# idro900ma.net
KiCad netlist of a schematic drawn in Altium Designer
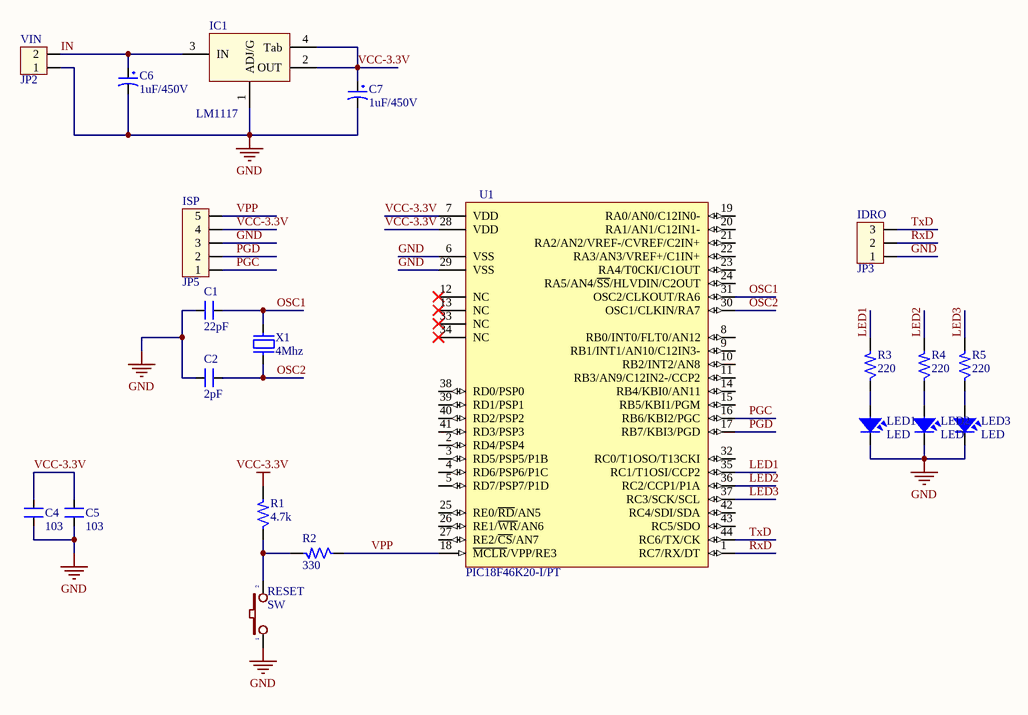
[diagram p0: idro900ma.SchDoc]

(export (version "E")
  (design (tool "Eeschema 10.0.6"))
  (components
    (comp (ref "C1")
      (value "22pF")
      (footprint "SM-0805")
      (description "Cap SMD")
      (libsource (lib "syhaunguyen") (part "CM"))
    )
    (comp (ref "C2")
      (value "2pF")
      (footprint "SM-0805")
      (description "Cap SMD")
      (libsource (lib "syhaunguyen") (part "CM"))
    )
    (comp (ref "C4")
      (value "103")
      (footprint "SM-0805")
      (description "Cap SMD")
      (libsource (lib "syhaunguyen") (part "CM"))
    )
    (comp (ref "C5")
      (value "103")
      (footprint "SM-0805")
      (description "Cap SMD")
      (libsource (lib "syhaunguyen") (part "CM"))
    )
    (comp (ref "C6")
      (value "1uF/450V")
      (footprint "SM-0805")
      (description "Cap 4700uF/50V")
      (libsource (lib "syhaunguyen") (part "CP8"))
    )
    (comp (ref "C7")
      (value "1uF/450V")
      (footprint "SM-0805")
      (description "Cap 4700uF/50V")
      (libsource (lib "syhaunguyen") (part "CP8"))
    )
    (comp (ref "IC1")
      (value "LM1117")
      (footprint "SOT223-4N")
      (description "3v3")
      (libsource (lib "syhaunguyen") (part "LM1117"))
    )
    (comp (ref "IDRO")
      (value "JP3")
      (footprint "CON3")
      (description "Connector 3")
      (libsource (lib "syhaunguyen") (part "Con3"))
    )
    (comp (ref "ISP")
      (value "JP5")
      (footprint "CON5")
      (description "Connector 5")
      (libsource (lib "syhaunguyen") (part "Con5"))
    )
    (comp (ref "LED1")
      (value "LED")
      (footprint "LED1206-Green")
      (description "LED Single colour Green and Red")
      (libsource (lib "syhaunguyen") (part "LED"))
    )
    (comp (ref "LED2")
      (value "LED")
      (footprint "LED1206-Green")
      (description "LED Single colour Green and Red")
      (libsource (lib "syhaunguyen") (part "LED"))
    )
    (comp (ref "LED3")
      (value "LED")
      (footprint "LED1206-Green")
      (description "LED Single colour Green and Red")
      (libsource (lib "syhaunguyen") (part "LED"))
    )
    (comp (ref "R1")
      (value "4.7k")
      (footprint "SM-0805")
      (description "Resistor 1/4W")
      (libsource (lib "syhaunguyen") (part "R"))
    )
    (comp (ref "R2")
      (value "330")
      (footprint "SM-0805")
      (description "Resistor 1/4W")
      (libsource (lib "syhaunguyen") (part "R"))
    )
    (comp (ref "R3")
      (value "220")
      (footprint "SM-0805")
      (description "Resistor 1/4W")
      (libsource (lib "syhaunguyen") (part "R"))
    )
    (comp (ref "R4")
      (value "220")
      (footprint "SM-0805")
      (description "Resistor 1/4W")
      (libsource (lib "syhaunguyen") (part "R"))
    )
    (comp (ref "R5")
      (value "220")
      (footprint "SM-0805")
      (description "Resistor 1/4W")
      (libsource (lib "syhaunguyen") (part "R"))
    )
    (comp (ref "RESET")
      (value "SW")
      (footprint "SW2")
      (description "Switch button 2 pin")
      (libsource (lib "syhaunguyen") (part "SW2"))
    )
    (comp (ref "U1")
      (value "PIC18F46K20-I/PT")
      (footprint "TQFP-PT44_N")
      (fields (field (name "PUBLISHER") "Altium Limited"))
      (libsource (lib "Microchip Microcontroller 8-Bit PIC18") (part "PIC18F46K20-I/PT"))
    )
    (comp (ref "VIN")
      (value "JP2")
      (footprint "CON2")
      (description "Connector 2")
      (libsource (lib "syhaunguyen") (part "Con2"))
    )
    (comp (ref "X1")
      (value "4Mhz")
      (footprint "XT2")
      (description "Crystal For all Crystal 2pin.")
      (libsource (lib "syhaunguyen") (part "XT2"))
    )
  )
  (nets
    (net (code "1") (name "/IN") (class "Default")
      (node (ref "C6") (pin "1") (pinfunction "1_1") (pintype "passive"))
      (node (ref "IC1") (pin "3") (pinfunction "IN_3") (pintype "passive"))
      (node (ref "VIN") (pin "2") (pinfunction "2_2") (pintype "passive"))
    )
    (net (code "2") (name "/LED1") (class "Default")
      (node (ref "R3") (pin "2") (pinfunction "2_2") (pintype "passive"))
      (node (ref "U1") (pin "35") (pinfunction "RC1/T1OSI/CCP2_35") (pintype "bidirectional"))
    )
    (net (code "3") (name "/LED2") (class "Default")
      (node (ref "R4") (pin "2") (pinfunction "2_2") (pintype "passive"))
      (node (ref "U1") (pin "36") (pinfunction "RC2/CCP1/P1A_36") (pintype "bidirectional"))
    )
    (net (code "4") (name "/LED3") (class "Default")
      (node (ref "R5") (pin "2") (pinfunction "2_2") (pintype "passive"))
      (node (ref "U1") (pin "37") (pinfunction "RC3/SCK/SCL_37") (pintype "bidirectional"))
    )
    (net (code "5") (name "/OSC1") (class "Default")
      (node (ref "C1") (pin "2") (pinfunction "2_2") (pintype "passive"))
      (node (ref "U1") (pin "31") (pinfunction "OSC2/CLKOUT/RA6_31") (pintype "bidirectional"))
      (node (ref "X1") (pin "2") (pinfunction "2_2") (pintype "passive"))
    )
    (net (code "6") (name "/OSC2") (class "Default")
      (node (ref "C2") (pin "2") (pinfunction "2_2") (pintype "passive"))
      (node (ref "U1") (pin "30") (pinfunction "OSC1/CLKIN/RA7_30") (pintype "bidirectional"))
      (node (ref "X1") (pin "1") (pinfunction "1_1") (pintype "passive"))
    )
    (net (code "7") (name "/PGC") (class "Default")
      (node (ref "ISP") (pin "1") (pinfunction "1_1") (pintype "passive"))
      (node (ref "U1") (pin "16") (pinfunction "RB6/KBI2/PGC_16") (pintype "bidirectional"))
    )
    (net (code "8") (name "/PGD") (class "Default")
      (node (ref "ISP") (pin "2") (pinfunction "2_2") (pintype "passive"))
      (node (ref "U1") (pin "17") (pinfunction "RB7/KBI3/PGD_17") (pintype "bidirectional"))
    )
    (net (code "9") (name "/RxD") (class "Default")
      (node (ref "IDRO") (pin "2") (pinfunction "2_2") (pintype "passive"))
      (node (ref "U1") (pin "1") (pinfunction "RC7/RX/DT_1") (pintype "bidirectional"))
    )
    (net (code "10") (name "/TxD") (class "Default")
      (node (ref "IDRO") (pin "3") (pinfunction "3_3") (pintype "passive"))
      (node (ref "U1") (pin "44") (pinfunction "RC6/TX/CK_44") (pintype "bidirectional"))
    )
    (net (code "11") (name "/VPP") (class "Default")
      (node (ref "ISP") (pin "5") (pinfunction "5_5") (pintype "passive"))
      (node (ref "R2") (pin "1") (pinfunction "1_1") (pintype "passive"))
      (node (ref "U1") (pin "18") (pinfunction "~{MCLR}/VPP/RE3_18") (pintype "input"))
    )
    (net (code "12") (name "GND") (class "Default")
      (node (ref "C1") (pin "1") (pinfunction "1_1") (pintype "passive"))
      (node (ref "C2") (pin "1") (pinfunction "1_1") (pintype "passive"))
      (node (ref "C4") (pin "1") (pinfunction "1_1") (pintype "passive"))
      (node (ref "C5") (pin "1") (pinfunction "1_1") (pintype "passive"))
      (node (ref "C6") (pin "2") (pinfunction "2_2") (pintype "passive"))
      (node (ref "C7") (pin "2") (pinfunction "2_2") (pintype "passive"))
      (node (ref "IC1") (pin "1") (pinfunction "ADJ/G_1") (pintype "passive"))
      (node (ref "IDRO") (pin "1") (pinfunction "1_1") (pintype "passive"))
      (node (ref "ISP") (pin "3") (pinfunction "3_3") (pintype "passive"))
      (node (ref "LED1") (pin "2") (pinfunction "2_2") (pintype "passive"))
      (node (ref "LED2") (pin "2") (pinfunction "2_2") (pintype "passive"))
      (node (ref "LED3") (pin "2") (pinfunction "2_2") (pintype "passive"))
      (node (ref "RESET") (pin "1") (pinfunction "1_1") (pintype "passive"))
      (node (ref "U1") (pin "29") (pinfunction "VSS_29") (pintype "power_in"))
      (node (ref "U1") (pin "6") (pinfunction "VSS_6") (pintype "power_in"))
      (node (ref "VIN") (pin "1") (pinfunction "1_1") (pintype "passive"))
    )
    (net (code "13") (name "Net-(LED1-Pad1)") (class "Default")
      (node (ref "LED1") (pin "1") (pinfunction "1_1") (pintype "passive"))
      (node (ref "R3") (pin "1") (pinfunction "1_1") (pintype "passive"))
    )
    (net (code "14") (name "Net-(LED2-Pad1)") (class "Default")
      (node (ref "LED2") (pin "1") (pinfunction "1_1") (pintype "passive"))
      (node (ref "R4") (pin "1") (pinfunction "1_1") (pintype "passive"))
    )
    (net (code "15") (name "Net-(LED3-Pad1)") (class "Default")
      (node (ref "LED3") (pin "1") (pinfunction "1_1") (pintype "passive"))
      (node (ref "R5") (pin "1") (pinfunction "1_1") (pintype "passive"))
    )
    (net (code "16") (name "Net-(R1-Pad1)") (class "Default")
      (node (ref "R1") (pin "1") (pinfunction "1_1") (pintype "passive"))
      (node (ref "R2") (pin "2") (pinfunction "2_2") (pintype "passive"))
      (node (ref "RESET") (pin "2") (pinfunction "2_2") (pintype "passive"))
    )
    (net (code "17") (name "VCC-3.3V") (class "Default")
      (node (ref "C4") (pin "2") (pinfunction "2_2") (pintype "passive"))
      (node (ref "C5") (pin "2") (pinfunction "2_2") (pintype "passive"))
      (node (ref "C7") (pin "1") (pinfunction "1_1") (pintype "passive"))
      (node (ref "IC1") (pin "2") (pinfunction "OUT_2") (pintype "passive"))
      (node (ref "IC1") (pin "4") (pinfunction "Tab_4") (pintype "passive"))
      (node (ref "ISP") (pin "4") (pinfunction "4_4") (pintype "passive"))
      (node (ref "R1") (pin "2") (pinfunction "2_2") (pintype "passive"))
      (node (ref "U1") (pin "28") (pinfunction "VDD_28") (pintype "power_in"))
      (node (ref "U1") (pin "7") (pinfunction "VDD_7") (pintype "power_in"))
    )
    (net (code "18") (name "unconnected-(U1-NC-Pad12)") (class "Default")
      (node (ref "U1") (pin "12") (pinfunction "NC_12") (pintype "passive+no_connect"))
    )
    (net (code "19") (name "unconnected-(U1-NC-Pad13)") (class "Default")
      (node (ref "U1") (pin "13") (pinfunction "NC_13") (pintype "passive+no_connect"))
    )
    (net (code "20") (name "unconnected-(U1-NC-Pad33)") (class "Default")
      (node (ref "U1") (pin "33") (pinfunction "NC_33") (pintype "passive+no_connect"))
    )
    (net (code "21") (name "unconnected-(U1-NC-Pad34)") (class "Default")
      (node (ref "U1") (pin "34") (pinfunction "NC_34") (pintype "passive+no_connect"))
    )
    (net (code "22") (name "unconnected-(U1-RA0{slash}AN0{slash}C12IN0--Pad19)") (class "Default")
      (node (ref "U1") (pin "19") (pinfunction "RA0/AN0/C12IN0-_19") (pintype "bidirectional"))
    )
    (net (code "23") (name "unconnected-(U1-RA1{slash}AN1{slash}C12IN1--Pad20)") (class "Default")
      (node (ref "U1") (pin "20") (pinfunction "RA1/AN1/C12IN1-_20") (pintype "bidirectional"))
    )
    (net (code "24") (name "unconnected-(U1-RA2{slash}AN2{slash}VREF-{slash}CVREF{slash}C2IN+-Pad21)") (class "Default")
      (node (ref "U1") (pin "21") (pinfunction "RA2/AN2/VREF-/CVREF/C2IN+_21") (pintype "bidirectional"))
    )
    (net (code "25") (name "unconnected-(U1-RA3{slash}AN3{slash}VREF+{slash}C1IN+-Pad22)") (class "Default")
      (node (ref "U1") (pin "22") (pinfunction "RA3/AN3/VREF+/C1IN+_22") (pintype "bidirectional"))
    )
    (net (code "26") (name "unconnected-(U1-RA4{slash}T0CKI{slash}C1OUT-Pad23)") (class "Default")
      (node (ref "U1") (pin "23") (pinfunction "RA4/T0CKI/C1OUT_23") (pintype "bidirectional"))
    )
    (net (code "27") (name "unconnected-(U1-RA5{slash}AN4{slash}~{SS}{slash}HLVDIN{slash}C2OUT-Pad24)") (class "Default")
      (node (ref "U1") (pin "24") (pinfunction "RA5/AN4/~{SS}/HLVDIN/C2OUT_24") (pintype "bidirectional"))
    )
    (net (code "28") (name "unconnected-(U1-RB0{slash}INT0{slash}FLT0{slash}AN12-Pad8)") (class "Default")
      (node (ref "U1") (pin "8") (pinfunction "RB0/INT0/FLT0/AN12_8") (pintype "bidirectional"))
    )
    (net (code "29") (name "unconnected-(U1-RB1{slash}INT1{slash}AN10{slash}C12IN3--Pad9)") (class "Default")
      (node (ref "U1") (pin "9") (pinfunction "RB1/INT1/AN10/C12IN3-_9") (pintype "bidirectional"))
    )
    (net (code "30") (name "unconnected-(U1-RB2{slash}INT2{slash}AN8-Pad10)") (class "Default")
      (node (ref "U1") (pin "10") (pinfunction "RB2/INT2/AN8_10") (pintype "bidirectional"))
    )
    (net (code "31") (name "unconnected-(U1-RB3{slash}AN9{slash}C12IN2-{slash}CCP2-Pad11)") (class "Default")
      (node (ref "U1") (pin "11") (pinfunction "RB3/AN9/C12IN2-/CCP2_11") (pintype "bidirectional"))
    )
    (net (code "32") (name "unconnected-(U1-RB4{slash}KBI0{slash}AN11-Pad14)") (class "Default")
      (node (ref "U1") (pin "14") (pinfunction "RB4/KBI0/AN11_14") (pintype "bidirectional"))
    )
    (net (code "33") (name "unconnected-(U1-RB5{slash}KBI1{slash}PGM-Pad15)") (class "Default")
      (node (ref "U1") (pin "15") (pinfunction "RB5/KBI1/PGM_15") (pintype "bidirectional"))
    )
    (net (code "34") (name "unconnected-(U1-RC0{slash}T1OSO{slash}T13CKI-Pad32)") (class "Default")
      (node (ref "U1") (pin "32") (pinfunction "RC0/T1OSO/T13CKI_32") (pintype "bidirectional"))
    )
    (net (code "35") (name "unconnected-(U1-RC4{slash}SDI{slash}SDA-Pad42)") (class "Default")
      (node (ref "U1") (pin "42") (pinfunction "RC4/SDI/SDA_42") (pintype "bidirectional"))
    )
    (net (code "36") (name "unconnected-(U1-RC5{slash}SDO-Pad43)") (class "Default")
      (node (ref "U1") (pin "43") (pinfunction "RC5/SDO_43") (pintype "bidirectional"))
    )
    (net (code "37") (name "unconnected-(U1-RD0{slash}PSP0-Pad38)") (class "Default")
      (node (ref "U1") (pin "38") (pinfunction "RD0/PSP0_38") (pintype "bidirectional"))
    )
    (net (code "38") (name "unconnected-(U1-RD1{slash}PSP1-Pad39)") (class "Default")
      (node (ref "U1") (pin "39") (pinfunction "RD1/PSP1_39") (pintype "bidirectional"))
    )
    (net (code "39") (name "unconnected-(U1-RD2{slash}PSP2-Pad40)") (class "Default")
      (node (ref "U1") (pin "40") (pinfunction "RD2/PSP2_40") (pintype "bidirectional"))
    )
    (net (code "40") (name "unconnected-(U1-RD3{slash}PSP3-Pad41)") (class "Default")
      (node (ref "U1") (pin "41") (pinfunction "RD3/PSP3_41") (pintype "bidirectional"))
    )
    (net (code "41") (name "unconnected-(U1-RD4{slash}PSP4-Pad2)") (class "Default")
      (node (ref "U1") (pin "2") (pinfunction "RD4/PSP4_2") (pintype "bidirectional"))
    )
    (net (code "42") (name "unconnected-(U1-RD5{slash}PSP5{slash}P1B-Pad3)") (class "Default")
      (node (ref "U1") (pin "3") (pinfunction "RD5/PSP5/P1B_3") (pintype "bidirectional"))
    )
    (net (code "43") (name "unconnected-(U1-RD6{slash}PSP6{slash}P1C-Pad4)") (class "Default")
      (node (ref "U1") (pin "4") (pinfunction "RD6/PSP6/P1C_4") (pintype "bidirectional"))
    )
    (net (code "44") (name "unconnected-(U1-RD7{slash}PSP7{slash}P1D-Pad5)") (class "Default")
      (node (ref "U1") (pin "5") (pinfunction "RD7/PSP7/P1D_5") (pintype "bidirectional"))
    )
    (net (code "45") (name "unconnected-(U1-RE0{slash}~{RD}{slash}AN5-Pad25)") (class "Default")
      (node (ref "U1") (pin "25") (pinfunction "RE0/~{RD}/AN5_25") (pintype "bidirectional"))
    )
    (net (code "46") (name "unconnected-(U1-RE1{slash}~{WR}{slash}AN6-Pad26)") (class "Default")
      (node (ref "U1") (pin "26") (pinfunction "RE1/~{WR}/AN6_26") (pintype "bidirectional"))
    )
    (net (code "47") (name "unconnected-(U1-RE2{slash}~{CS}{slash}AN7-Pad27)") (class "Default")
      (node (ref "U1") (pin "27") (pinfunction "RE2/~{CS}/AN7_27") (pintype "bidirectional"))
    )
  )
)
